# control_board.net
KiCad netlist of a schematic drawn in EAGLE
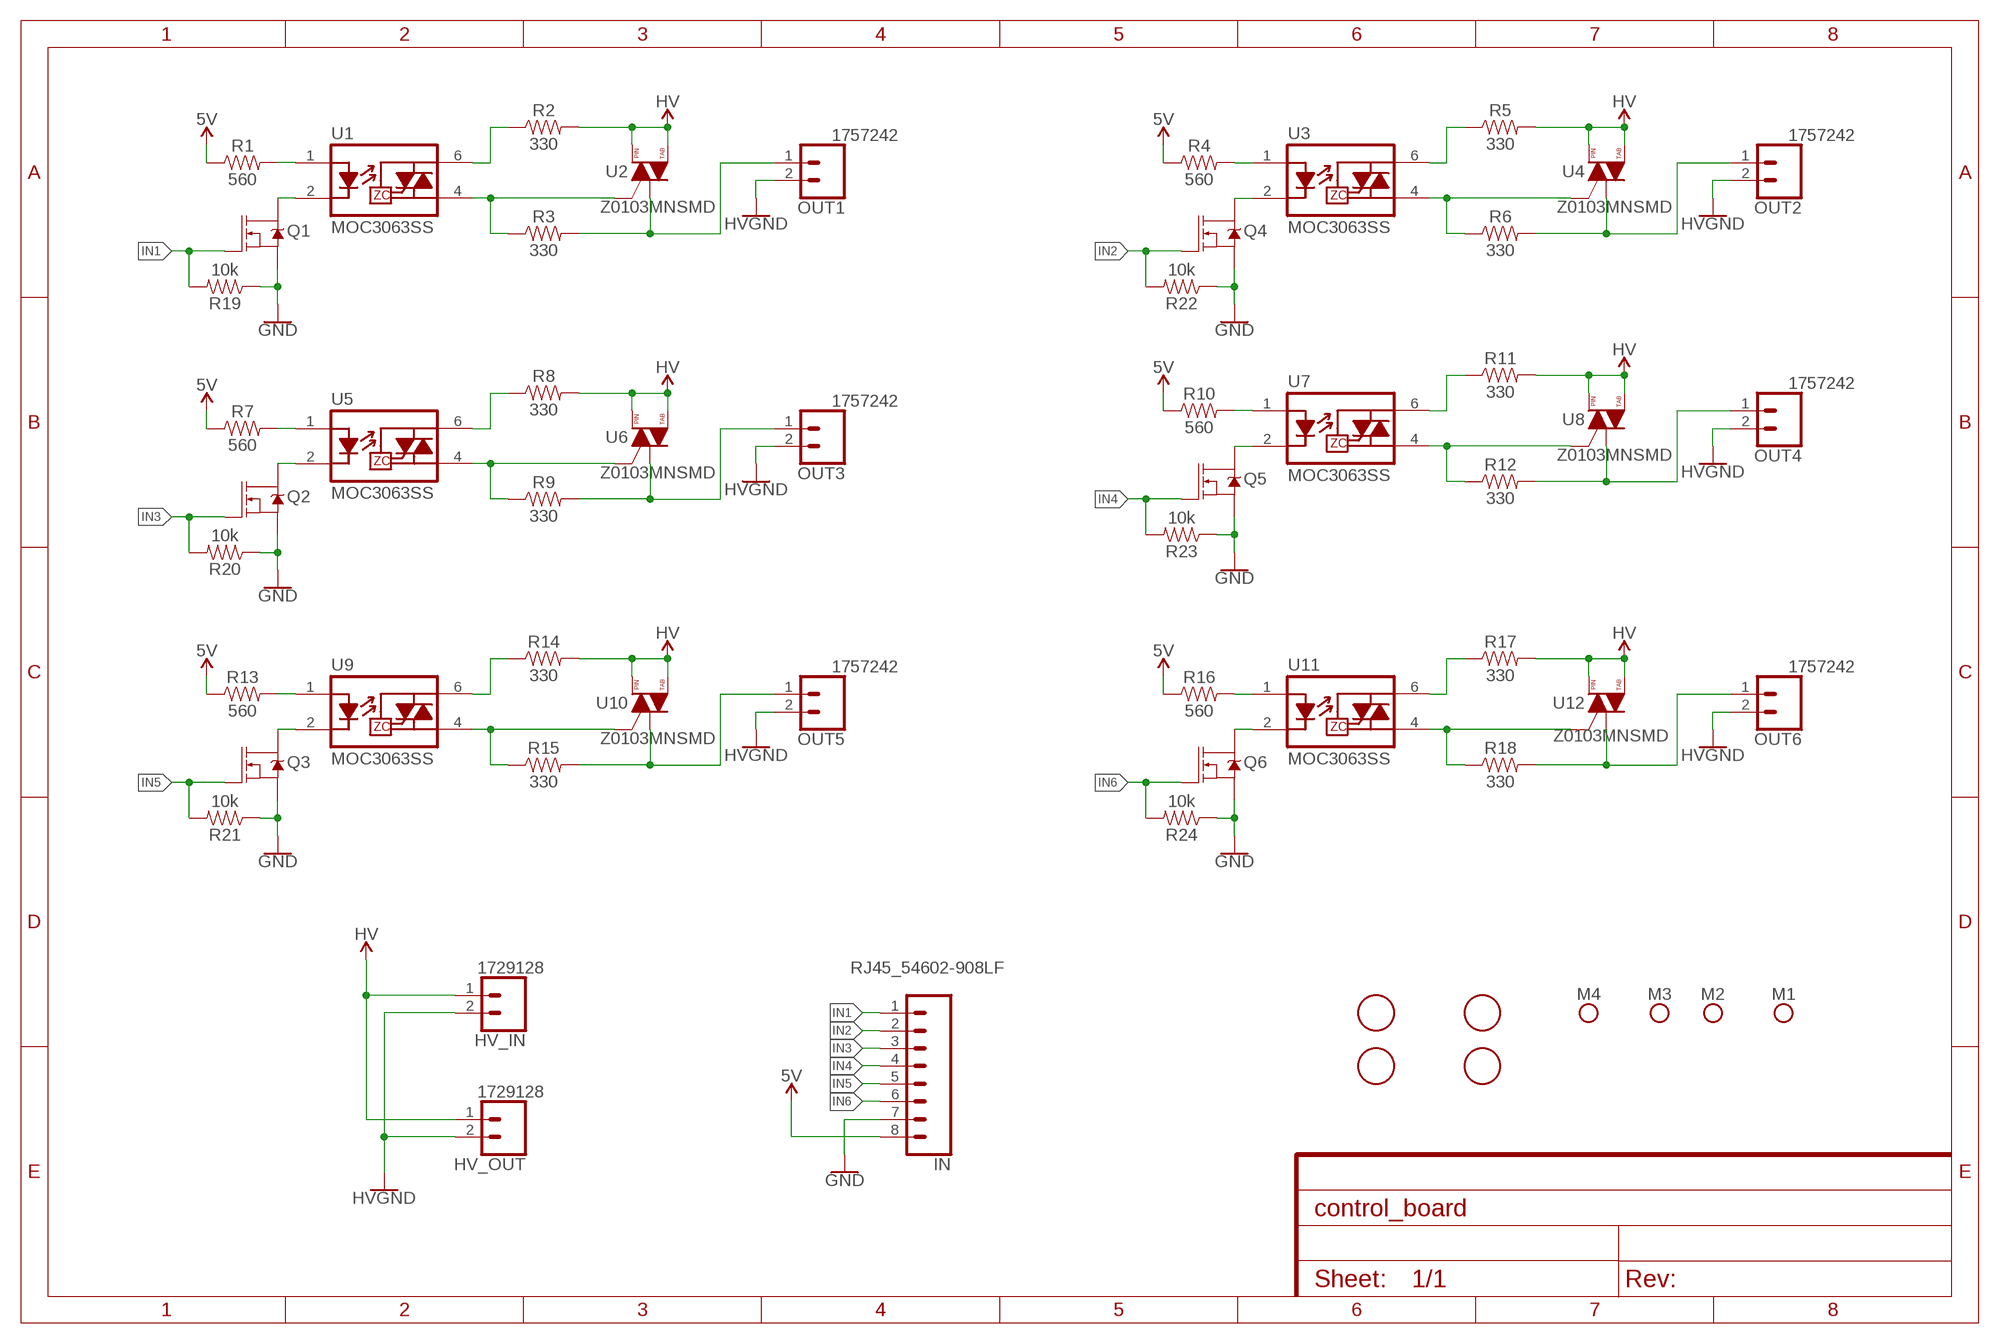
[diagram p0: schematic, sheet 1]

(export (version "E")
  (design (tool "Eeschema 10.0.6"))
  (components
    (comp (ref "HV_IN")
      (value "1729128")
      (footprint "eagle-import:1729128")
      (fields (field (name "MOUSER_PART_NUMBER") "651-1729128"))
      (libsource (lib "eagle-import") (part "1729128"))
    )
    (comp (ref "HV_OUT")
      (value "1729128")
      (footprint "eagle-import:1729128")
      (fields (field (name "MOUSER_PART_NUMBER") "651-1729128"))
      (libsource (lib "eagle-import") (part "1729128"))
    )
    (comp (ref "IN")
      (value "RJ45_54602-908LF")
      (footprint "eagle-import:54602-908LF")
      (fields
        (field (name "MANUFACTURER_PART_NUMBER") "54602-908LF")
        (field (name "JLC_PART_NUMBER") "C2847314")
      )
      (libsource (lib "eagle-import") (part "RJ45_54602-908LF"))
    )
    (comp (ref "M1")
      (value "NO_BOM")
      (footprint "eagle-import:HOLE_ISOLATED_M2.5")
      (libsource (lib "eagle-import") (part "HOLE_ISOLATED-M2.5"))
    )
    (comp (ref "M2")
      (value "NO_BOM")
      (footprint "eagle-import:HOLE_ISOLATED_M2.5")
      (libsource (lib "eagle-import") (part "HOLE_ISOLATED-M2.5"))
    )
    (comp (ref "M3")
      (value "NO_BOM")
      (footprint "eagle-import:HOLE_ISOLATED_M2.5")
      (libsource (lib "eagle-import") (part "HOLE_ISOLATED-M2.5"))
    )
    (comp (ref "M4")
      (value "NO_BOM")
      (footprint "eagle-import:HOLE_ISOLATED_M2.5")
      (libsource (lib "eagle-import") (part "HOLE_ISOLATED-M2.5"))
    )
    (comp (ref "OUT1")
      (value "1757242")
      (footprint "eagle-import:PHOENIX_1757242")
      (fields (field (name "DIGI-KEY_PART_NUMBER") "277-1106-ND") (field (name "JLC_PART_NUMBER") "C90074"))
      (libsource (lib "eagle-import") (part "1757242"))
    )
    (comp (ref "OUT2")
      (value "1757242")
      (footprint "eagle-import:PHOENIX_1757242")
      (fields (field (name "DIGI-KEY_PART_NUMBER") "277-1106-ND") (field (name "JLC_PART_NUMBER") "C90074"))
      (libsource (lib "eagle-import") (part "1757242"))
    )
    (comp (ref "OUT3")
      (value "1757242")
      (footprint "eagle-import:PHOENIX_1757242")
      (fields (field (name "DIGI-KEY_PART_NUMBER") "277-1106-ND") (field (name "JLC_PART_NUMBER") "C90074"))
      (libsource (lib "eagle-import") (part "1757242"))
    )
    (comp (ref "OUT4")
      (value "1757242")
      (footprint "eagle-import:PHOENIX_1757242")
      (fields (field (name "DIGI-KEY_PART_NUMBER") "277-1106-ND") (field (name "JLC_PART_NUMBER") "C90074"))
      (libsource (lib "eagle-import") (part "1757242"))
    )
    (comp (ref "OUT5")
      (value "1757242")
      (footprint "eagle-import:PHOENIX_1757242")
      (fields (field (name "DIGI-KEY_PART_NUMBER") "277-1106-ND") (field (name "JLC_PART_NUMBER") "C90074"))
      (libsource (lib "eagle-import") (part "1757242"))
    )
    (comp (ref "OUT6")
      (value "1757242")
      (footprint "eagle-import:PHOENIX_1757242")
      (fields (field (name "DIGI-KEY_PART_NUMBER") "277-1106-ND") (field (name "JLC_PART_NUMBER") "C90074"))
      (libsource (lib "eagle-import") (part "1757242"))
    )
    (comp (ref "Q1")
      (value "AO3400A")
      (footprint "eagle-import:SOT95P280X125-3N")
      (fields (field (name "JLC_PART_NUMBER") "C20917"))
      (libsource (lib "eagle-import") (part "AO3400A"))
    )
    (comp (ref "Q2")
      (value "AO3400A")
      (footprint "eagle-import:SOT95P280X125-3N")
      (fields (field (name "JLC_PART_NUMBER") "C20917"))
      (libsource (lib "eagle-import") (part "AO3400A"))
    )
    (comp (ref "Q3")
      (value "AO3400A")
      (footprint "eagle-import:SOT95P280X125-3N")
      (fields (field (name "JLC_PART_NUMBER") "C20917"))
      (libsource (lib "eagle-import") (part "AO3400A"))
    )
    (comp (ref "Q4")
      (value "AO3400A")
      (footprint "eagle-import:SOT95P280X125-3N")
      (fields (field (name "JLC_PART_NUMBER") "C20917"))
      (libsource (lib "eagle-import") (part "AO3400A"))
    )
    (comp (ref "Q5")
      (value "AO3400A")
      (footprint "eagle-import:SOT95P280X125-3N")
      (fields (field (name "JLC_PART_NUMBER") "C20917"))
      (libsource (lib "eagle-import") (part "AO3400A"))
    )
    (comp (ref "Q6")
      (value "AO3400A")
      (footprint "eagle-import:SOT95P280X125-3N")
      (fields (field (name "JLC_PART_NUMBER") "C20917"))
      (libsource (lib "eagle-import") (part "AO3400A"))
    )
    (comp (ref "R1")
      (value "560")
      (footprint "eagle-import:R0603")
      (fields (field (name "JLC_PART_NUMBER") "C23204"))
      (libsource (lib "eagle-import") (part "RES-1/10W-5%-0603"))
    )
    (comp (ref "R2")
      (value "330")
      (footprint "eagle-import:R0603")
      (fields (field (name "JLC_PART_NUMBER") "C23138"))
      (libsource (lib "eagle-import") (part "RES-1/10W-5%-0603"))
    )
    (comp (ref "R3")
      (value "330")
      (footprint "eagle-import:R0603")
      (fields (field (name "JLC_PART_NUMBER") "C23138"))
      (libsource (lib "eagle-import") (part "RES-1/10W-5%-0603"))
    )
    (comp (ref "R4")
      (value "560")
      (footprint "eagle-import:R0603")
      (fields (field (name "JLC_PART_NUMBER") "C23204"))
      (libsource (lib "eagle-import") (part "RES-1/10W-5%-0603"))
    )
    (comp (ref "R5")
      (value "330")
      (footprint "eagle-import:R0603")
      (fields (field (name "JLC_PART_NUMBER") "C23138"))
      (libsource (lib "eagle-import") (part "RES-1/10W-5%-0603"))
    )
    (comp (ref "R6")
      (value "330")
      (footprint "eagle-import:R0603")
      (fields (field (name "JLC_PART_NUMBER") "C23138"))
      (libsource (lib "eagle-import") (part "RES-1/10W-5%-0603"))
    )
    (comp (ref "R7")
      (value "560")
      (footprint "eagle-import:R0603")
      (fields (field (name "JLC_PART_NUMBER") "C23204"))
      (libsource (lib "eagle-import") (part "RES-1/10W-5%-0603"))
    )
    (comp (ref "R8")
      (value "330")
      (footprint "eagle-import:R0603")
      (fields (field (name "JLC_PART_NUMBER") "C23138"))
      (libsource (lib "eagle-import") (part "RES-1/10W-5%-0603"))
    )
    (comp (ref "R9")
      (value "330")
      (footprint "eagle-import:R0603")
      (fields (field (name "JLC_PART_NUMBER") "C23138"))
      (libsource (lib "eagle-import") (part "RES-1/10W-5%-0603"))
    )
    (comp (ref "R10")
      (value "560")
      (footprint "eagle-import:R0603")
      (fields (field (name "JLC_PART_NUMBER") "C23204"))
      (libsource (lib "eagle-import") (part "RES-1/10W-5%-0603"))
    )
    (comp (ref "R11")
      (value "330")
      (footprint "eagle-import:R0603")
      (fields (field (name "JLC_PART_NUMBER") "C23138"))
      (libsource (lib "eagle-import") (part "RES-1/10W-5%-0603"))
    )
    (comp (ref "R12")
      (value "330")
      (footprint "eagle-import:R0603")
      (fields (field (name "JLC_PART_NUMBER") "C23138"))
      (libsource (lib "eagle-import") (part "RES-1/10W-5%-0603"))
    )
    (comp (ref "R13")
      (value "560")
      (footprint "eagle-import:R0603")
      (fields (field (name "JLC_PART_NUMBER") "C23204"))
      (libsource (lib "eagle-import") (part "RES-1/10W-5%-0603"))
    )
    (comp (ref "R14")
      (value "330")
      (footprint "eagle-import:R0603")
      (fields (field (name "JLC_PART_NUMBER") "C23138"))
      (libsource (lib "eagle-import") (part "RES-1/10W-5%-0603"))
    )
    (comp (ref "R15")
      (value "330")
      (footprint "eagle-import:R0603")
      (fields (field (name "JLC_PART_NUMBER") "C23138"))
      (libsource (lib "eagle-import") (part "RES-1/10W-5%-0603"))
    )
    (comp (ref "R16")
      (value "560")
      (footprint "eagle-import:R0603")
      (fields (field (name "JLC_PART_NUMBER") "C23204"))
      (libsource (lib "eagle-import") (part "RES-1/10W-5%-0603"))
    )
    (comp (ref "R17")
      (value "330")
      (footprint "eagle-import:R0603")
      (fields (field (name "JLC_PART_NUMBER") "C23138"))
      (libsource (lib "eagle-import") (part "RES-1/10W-5%-0603"))
    )
    (comp (ref "R18")
      (value "330")
      (footprint "eagle-import:R0603")
      (fields (field (name "JLC_PART_NUMBER") "C23138"))
      (libsource (lib "eagle-import") (part "RES-1/10W-5%-0603"))
    )
    (comp (ref "R19")
      (value "10k")
      (footprint "eagle-import:R0603")
      (fields (field (name "JLC_PART_NUMBER") "C25804"))
      (libsource (lib "eagle-import") (part "RES-1/10W-5%-0603"))
    )
    (comp (ref "R20")
      (value "10k")
      (footprint "eagle-import:R0603")
      (fields (field (name "JLC_PART_NUMBER") "C25804"))
      (libsource (lib "eagle-import") (part "RES-1/10W-5%-0603"))
    )
    (comp (ref "R21")
      (value "10k")
      (footprint "eagle-import:R0603")
      (fields (field (name "JLC_PART_NUMBER") "C25804"))
      (libsource (lib "eagle-import") (part "RES-1/10W-5%-0603"))
    )
    (comp (ref "R22")
      (value "10k")
      (footprint "eagle-import:R0603")
      (fields (field (name "JLC_PART_NUMBER") "C25804"))
      (libsource (lib "eagle-import") (part "RES-1/10W-5%-0603"))
    )
    (comp (ref "R23")
      (value "10k")
      (footprint "eagle-import:R0603")
      (fields (field (name "JLC_PART_NUMBER") "C25804"))
      (libsource (lib "eagle-import") (part "RES-1/10W-5%-0603"))
    )
    (comp (ref "R24")
      (value "10k")
      (footprint "eagle-import:R0603")
      (fields (field (name "JLC_PART_NUMBER") "C25804"))
      (libsource (lib "eagle-import") (part "RES-1/10W-5%-0603"))
    )
    (comp (ref "T1")
      (value "NO_BOM")
      (footprint "eagle-import:JLC_TOOLING_HOLE")
      (libsource (lib "eagle-import") (part "JLC_TOOLING_HOLE"))
    )
    (comp (ref "T2")
      (value "NO_BOM")
      (footprint "eagle-import:JLC_TOOLING_HOLE")
      (libsource (lib "eagle-import") (part "JLC_TOOLING_HOLE"))
    )
    (comp (ref "T3")
      (value "NO_BOM")
      (footprint "eagle-import:JLC_TOOLING_HOLE")
      (libsource (lib "eagle-import") (part "JLC_TOOLING_HOLE"))
    )
    (comp (ref "T4")
      (value "NO_BOM")
      (footprint "eagle-import:JLC_TOOLING_HOLE")
      (libsource (lib "eagle-import") (part "JLC_TOOLING_HOLE"))
    )
    (comp (ref "U1")
      (value "MOC3063SS")
      (footprint "eagle-import:DIP8SMD")
      (fields (field (name "MANUFACTURER_PART_NUMBER") "MOC3063S") (field (name "JLC_PART_NUMBER") "C77950"))
      (libsource (lib "eagle-import") (part "MOC3063SS"))
    )
    (comp (ref "U2")
      (value "Z0103MNSMD")
      (footprint "eagle-import:SOT223")
      (fields
        (field (name "MANUFACTURER_PART_NUMBER") "Z0103MN 5AA4")
        (field (name "JLC_PART_NUMBER") "C163595")
      )
      (libsource (lib "eagle-import") (part "Z0103MNSMD"))
    )
    (comp (ref "U3")
      (value "MOC3063SS")
      (footprint "eagle-import:DIP8SMD")
      (fields (field (name "MANUFACTURER_PART_NUMBER") "MOC3063S") (field (name "JLC_PART_NUMBER") "C77950"))
      (libsource (lib "eagle-import") (part "MOC3063SS"))
    )
    (comp (ref "U4")
      (value "Z0103MNSMD")
      (footprint "eagle-import:SOT223")
      (fields
        (field (name "MANUFACTURER_PART_NUMBER") "Z0103MN 5AA4")
        (field (name "JLC_PART_NUMBER") "C163595")
      )
      (libsource (lib "eagle-import") (part "Z0103MNSMD"))
    )
    (comp (ref "U5")
      (value "MOC3063SS")
      (footprint "eagle-import:DIP8SMD")
      (fields (field (name "MANUFACTURER_PART_NUMBER") "MOC3063S") (field (name "JLC_PART_NUMBER") "C77950"))
      (libsource (lib "eagle-import") (part "MOC3063SS"))
    )
    (comp (ref "U6")
      (value "Z0103MNSMD")
      (footprint "eagle-import:SOT223")
      (fields
        (field (name "MANUFACTURER_PART_NUMBER") "Z0103MN 5AA4")
        (field (name "JLC_PART_NUMBER") "C163595")
      )
      (libsource (lib "eagle-import") (part "Z0103MNSMD"))
    )
    (comp (ref "U7")
      (value "MOC3063SS")
      (footprint "eagle-import:DIP8SMD")
      (fields (field (name "MANUFACTURER_PART_NUMBER") "MOC3063S") (field (name "JLC_PART_NUMBER") "C77950"))
      (libsource (lib "eagle-import") (part "MOC3063SS"))
    )
    (comp (ref "U8")
      (value "Z0103MNSMD")
      (footprint "eagle-import:SOT223")
      (fields
        (field (name "MANUFACTURER_PART_NUMBER") "Z0103MN 5AA4")
        (field (name "JLC_PART_NUMBER") "C163595")
      )
      (libsource (lib "eagle-import") (part "Z0103MNSMD"))
    )
    (comp (ref "U9")
      (value "MOC3063SS")
      (footprint "eagle-import:DIP8SMD")
      (fields (field (name "MANUFACTURER_PART_NUMBER") "MOC3063S") (field (name "JLC_PART_NUMBER") "C77950"))
      (libsource (lib "eagle-import") (part "MOC3063SS"))
    )
    (comp (ref "U10")
      (value "Z0103MNSMD")
      (footprint "eagle-import:SOT223")
      (fields
        (field (name "MANUFACTURER_PART_NUMBER") "Z0103MN 5AA4")
        (field (name "JLC_PART_NUMBER") "C163595")
      )
      (libsource (lib "eagle-import") (part "Z0103MNSMD"))
    )
    (comp (ref "U11")
      (value "MOC3063SS")
      (footprint "eagle-import:DIP8SMD")
      (fields (field (name "MANUFACTURER_PART_NUMBER") "MOC3063S") (field (name "JLC_PART_NUMBER") "C77950"))
      (libsource (lib "eagle-import") (part "MOC3063SS"))
    )
    (comp (ref "U12")
      (value "Z0103MNSMD")
      (footprint "eagle-import:SOT223")
      (fields
        (field (name "MANUFACTURER_PART_NUMBER") "Z0103MN 5AA4")
        (field (name "JLC_PART_NUMBER") "C163595")
      )
      (libsource (lib "eagle-import") (part "Z0103MNSMD"))
    )
  )
  (nets
    (net (code "1") (name "5V") (class "Default")
      (node (ref "IN") (pin "8") (pinfunction "8_8") (pintype "passive"))
      (node (ref "R1") (pin "1") (pinfunction "1_1") (pintype "passive"))
      (node (ref "R10") (pin "1") (pinfunction "1_1") (pintype "passive"))
      (node (ref "R13") (pin "1") (pinfunction "1_1") (pintype "passive"))
      (node (ref "R16") (pin "1") (pinfunction "1_1") (pintype "passive"))
      (node (ref "R4") (pin "1") (pinfunction "1_1") (pintype "passive"))
      (node (ref "R7") (pin "1") (pinfunction "1_1") (pintype "passive"))
    )
    (net (code "2") (name "GND") (class "Default")
      (node (ref "IN") (pin "7") (pinfunction "7_7") (pintype "passive"))
      (node (ref "Q1") (pin "2") (pinfunction "S_2") (pintype "passive"))
      (node (ref "Q2") (pin "2") (pinfunction "S_2") (pintype "passive"))
      (node (ref "Q3") (pin "2") (pinfunction "S_2") (pintype "passive"))
      (node (ref "Q4") (pin "2") (pinfunction "S_2") (pintype "passive"))
      (node (ref "Q5") (pin "2") (pinfunction "S_2") (pintype "passive"))
      (node (ref "Q6") (pin "2") (pinfunction "S_2") (pintype "passive"))
      (node (ref "R19") (pin "1") (pinfunction "1_1") (pintype "passive"))
      (node (ref "R20") (pin "1") (pinfunction "1_1") (pintype "passive"))
      (node (ref "R21") (pin "1") (pinfunction "1_1") (pintype "passive"))
      (node (ref "R22") (pin "1") (pinfunction "1_1") (pintype "passive"))
      (node (ref "R23") (pin "1") (pinfunction "1_1") (pintype "passive"))
      (node (ref "R24") (pin "1") (pinfunction "1_1") (pintype "passive"))
    )
    (net (code "3") (name "HV") (class "Default")
      (node (ref "HV_IN") (pin "1") (pinfunction "1_1") (pintype "passive"))
      (node (ref "HV_OUT") (pin "1") (pinfunction "1_1") (pintype "passive"))
      (node (ref "R11") (pin "2") (pinfunction "2_2") (pintype "passive"))
      (node (ref "R14") (pin "2") (pinfunction "2_2") (pintype "passive"))
      (node (ref "R17") (pin "2") (pinfunction "2_2") (pintype "passive"))
      (node (ref "R2") (pin "2") (pinfunction "2_2") (pintype "passive"))
      (node (ref "R5") (pin "2") (pinfunction "2_2") (pintype "passive"))
      (node (ref "R8") (pin "2") (pinfunction "2_2") (pintype "passive"))
      (node (ref "U10") (pin "2") (pinfunction "T2_2") (pintype "passive"))
      (node (ref "U10") (pin "4") (pinfunction "T2_4") (pintype "passive"))
      (node (ref "U12") (pin "2") (pinfunction "T2_2") (pintype "passive"))
      (node (ref "U12") (pin "4") (pinfunction "T2_4") (pintype "passive"))
      (node (ref "U2") (pin "2") (pinfunction "T2_2") (pintype "passive"))
      (node (ref "U2") (pin "4") (pinfunction "T2_4") (pintype "passive"))
      (node (ref "U4") (pin "2") (pinfunction "T2_2") (pintype "passive"))
      (node (ref "U4") (pin "4") (pinfunction "T2_4") (pintype "passive"))
      (node (ref "U6") (pin "2") (pinfunction "T2_2") (pintype "passive"))
      (node (ref "U6") (pin "4") (pinfunction "T2_4") (pintype "passive"))
      (node (ref "U8") (pin "2") (pinfunction "T2_2") (pintype "passive"))
      (node (ref "U8") (pin "4") (pinfunction "T2_4") (pintype "passive"))
    )
    (net (code "4") (name "HVGND") (class "Default")
      (node (ref "HV_IN") (pin "2") (pinfunction "2_2") (pintype "passive"))
      (node (ref "HV_OUT") (pin "2") (pinfunction "2_2") (pintype "passive"))
      (node (ref "OUT1") (pin "2") (pinfunction "2_2") (pintype "passive"))
      (node (ref "OUT2") (pin "2") (pinfunction "2_2") (pintype "passive"))
      (node (ref "OUT3") (pin "2") (pinfunction "2_2") (pintype "passive"))
      (node (ref "OUT4") (pin "2") (pinfunction "2_2") (pintype "passive"))
      (node (ref "OUT5") (pin "2") (pinfunction "2_2") (pintype "passive"))
      (node (ref "OUT6") (pin "2") (pinfunction "2_2") (pintype "passive"))
    )
    (net (code "5") (name "IN1") (class "Default")
      (node (ref "IN") (pin "1") (pinfunction "1_1") (pintype "passive"))
      (node (ref "Q1") (pin "1") (pinfunction "G_1") (pintype "passive"))
      (node (ref "R19") (pin "2") (pinfunction "2_2") (pintype "passive"))
    )
    (net (code "6") (name "IN2") (class "Default")
      (node (ref "IN") (pin "2") (pinfunction "2_2") (pintype "passive"))
      (node (ref "Q4") (pin "1") (pinfunction "G_1") (pintype "passive"))
      (node (ref "R22") (pin "2") (pinfunction "2_2") (pintype "passive"))
    )
    (net (code "7") (name "IN3") (class "Default")
      (node (ref "IN") (pin "3") (pinfunction "3_3") (pintype "passive"))
      (node (ref "Q2") (pin "1") (pinfunction "G_1") (pintype "passive"))
      (node (ref "R20") (pin "2") (pinfunction "2_2") (pintype "passive"))
    )
    (net (code "8") (name "IN4") (class "Default")
      (node (ref "IN") (pin "4") (pinfunction "4_4") (pintype "passive"))
      (node (ref "Q5") (pin "1") (pinfunction "G_1") (pintype "passive"))
      (node (ref "R23") (pin "2") (pinfunction "2_2") (pintype "passive"))
    )
    (net (code "9") (name "IN5") (class "Default")
      (node (ref "IN") (pin "5") (pinfunction "5_5") (pintype "passive"))
      (node (ref "Q3") (pin "1") (pinfunction "G_1") (pintype "passive"))
      (node (ref "R21") (pin "2") (pinfunction "2_2") (pintype "passive"))
    )
    (net (code "10") (name "IN6") (class "Default")
      (node (ref "IN") (pin "6") (pinfunction "6_6") (pintype "passive"))
      (node (ref "Q6") (pin "1") (pinfunction "G_1") (pintype "passive"))
      (node (ref "R24") (pin "2") (pinfunction "2_2") (pintype "passive"))
    )
    (net (code "11") (name "Net-(Q1-D)") (class "Default")
      (node (ref "Q1") (pin "3") (pinfunction "D_3") (pintype "passive"))
      (node (ref "U1") (pin "2") (pinfunction "K_2") (pintype "bidirectional"))
    )
    (net (code "12") (name "Net-(Q2-D)") (class "Default")
      (node (ref "Q2") (pin "3") (pinfunction "D_3") (pintype "passive"))
      (node (ref "U5") (pin "2") (pinfunction "K_2") (pintype "bidirectional"))
    )
    (net (code "13") (name "Net-(Q3-D)") (class "Default")
      (node (ref "Q3") (pin "3") (pinfunction "D_3") (pintype "passive"))
      (node (ref "U9") (pin "2") (pinfunction "K_2") (pintype "bidirectional"))
    )
    (net (code "14") (name "Net-(Q4-D)") (class "Default")
      (node (ref "Q4") (pin "3") (pinfunction "D_3") (pintype "passive"))
      (node (ref "U3") (pin "2") (pinfunction "K_2") (pintype "bidirectional"))
    )
    (net (code "15") (name "Net-(Q5-D)") (class "Default")
      (node (ref "Q5") (pin "3") (pinfunction "D_3") (pintype "passive"))
      (node (ref "U7") (pin "2") (pinfunction "K_2") (pintype "bidirectional"))
    )
    (net (code "16") (name "Net-(Q6-D)") (class "Default")
      (node (ref "Q6") (pin "3") (pinfunction "D_3") (pintype "passive"))
      (node (ref "U11") (pin "2") (pinfunction "K_2") (pintype "bidirectional"))
    )
    (net (code "17") (name "Net-(U1-A)") (class "Default")
      (node (ref "R1") (pin "2") (pinfunction "2_2") (pintype "passive"))
      (node (ref "U1") (pin "1") (pinfunction "A_1") (pintype "bidirectional"))
    )
    (net (code "18") (name "Net-(U1-T1)") (class "Default")
      (node (ref "R2") (pin "1") (pinfunction "1_1") (pintype "passive"))
      (node (ref "U1") (pin "6") (pinfunction "T1_6") (pintype "bidirectional"))
    )
    (net (code "19") (name "Net-(U1-T2)") (class "Default")
      (node (ref "R3") (pin "1") (pinfunction "1_1") (pintype "passive"))
      (node (ref "U1") (pin "4") (pinfunction "T2_4") (pintype "bidirectional"))
      (node (ref "U2") (pin "3") (pinfunction "G_3") (pintype "bidirectional"))
    )
    (net (code "20") (name "Net-(U2-T1)") (class "Default")
      (node (ref "OUT1") (pin "1") (pinfunction "1_1") (pintype "passive"))
      (node (ref "R3") (pin "2") (pinfunction "2_2") (pintype "passive"))
      (node (ref "U2") (pin "1") (pinfunction "T1_1") (pintype "bidirectional"))
    )
    (net (code "21") (name "Net-(U3-A)") (class "Default")
      (node (ref "R4") (pin "2") (pinfunction "2_2") (pintype "passive"))
      (node (ref "U3") (pin "1") (pinfunction "A_1") (pintype "bidirectional"))
    )
    (net (code "22") (name "Net-(U3-T1)") (class "Default")
      (node (ref "R5") (pin "1") (pinfunction "1_1") (pintype "passive"))
      (node (ref "U3") (pin "6") (pinfunction "T1_6") (pintype "bidirectional"))
    )
    (net (code "23") (name "Net-(U3-T2)") (class "Default")
      (node (ref "R6") (pin "1") (pinfunction "1_1") (pintype "passive"))
      (node (ref "U3") (pin "4") (pinfunction "T2_4") (pintype "bidirectional"))
      (node (ref "U4") (pin "3") (pinfunction "G_3") (pintype "bidirectional"))
    )
    (net (code "24") (name "Net-(U4-T1)") (class "Default")
      (node (ref "OUT2") (pin "1") (pinfunction "1_1") (pintype "passive"))
      (node (ref "R6") (pin "2") (pinfunction "2_2") (pintype "passive"))
      (node (ref "U4") (pin "1") (pinfunction "T1_1") (pintype "bidirectional"))
    )
    (net (code "25") (name "Net-(U5-A)") (class "Default")
      (node (ref "R7") (pin "2") (pinfunction "2_2") (pintype "passive"))
      (node (ref "U5") (pin "1") (pinfunction "A_1") (pintype "bidirectional"))
    )
    (net (code "26") (name "Net-(U5-T1)") (class "Default")
      (node (ref "R8") (pin "1") (pinfunction "1_1") (pintype "passive"))
      (node (ref "U5") (pin "6") (pinfunction "T1_6") (pintype "bidirectional"))
    )
    (net (code "27") (name "Net-(U5-T2)") (class "Default")
      (node (ref "R9") (pin "1") (pinfunction "1_1") (pintype "passive"))
      (node (ref "U5") (pin "4") (pinfunction "T2_4") (pintype "bidirectional"))
      (node (ref "U6") (pin "3") (pinfunction "G_3") (pintype "bidirectional"))
    )
    (net (code "28") (name "Net-(U6-T1)") (class "Default")
      (node (ref "OUT3") (pin "1") (pinfunction "1_1") (pintype "passive"))
      (node (ref "R9") (pin "2") (pinfunction "2_2") (pintype "passive"))
      (node (ref "U6") (pin "1") (pinfunction "T1_1") (pintype "bidirectional"))
    )
    (net (code "29") (name "Net-(U7-A)") (class "Default")
      (node (ref "R10") (pin "2") (pinfunction "2_2") (pintype "passive"))
      (node (ref "U7") (pin "1") (pinfunction "A_1") (pintype "bidirectional"))
    )
    (net (code "30") (name "Net-(U7-T1)") (class "Default")
      (node (ref "R11") (pin "1") (pinfunction "1_1") (pintype "passive"))
      (node (ref "U7") (pin "6") (pinfunction "T1_6") (pintype "bidirectional"))
    )
    (net (code "31") (name "Net-(U7-T2)") (class "Default")
      (node (ref "R12") (pin "1") (pinfunction "1_1") (pintype "passive"))
      (node (ref "U7") (pin "4") (pinfunction "T2_4") (pintype "bidirectional"))
      (node (ref "U8") (pin "3") (pinfunction "G_3") (pintype "bidirectional"))
    )
    (net (code "32") (name "Net-(U8-T1)") (class "Default")
      (node (ref "OUT4") (pin "1") (pinfunction "1_1") (pintype "passive"))
      (node (ref "R12") (pin "2") (pinfunction "2_2") (pintype "passive"))
      (node (ref "U8") (pin "1") (pinfunction "T1_1") (pintype "bidirectional"))
    )
    (net (code "33") (name "Net-(U9-A)") (class "Default")
      (node (ref "R13") (pin "2") (pinfunction "2_2") (pintype "passive"))
      (node (ref "U9") (pin "1") (pinfunction "A_1") (pintype "bidirectional"))
    )
    (net (code "34") (name "Net-(U9-T1)") (class "Default")
      (node (ref "R14") (pin "1") (pinfunction "1_1") (pintype "passive"))
      (node (ref "U9") (pin "6") (pinfunction "T1_6") (pintype "bidirectional"))
    )
    (net (code "35") (name "Net-(U10-G)") (class "Default")
      (node (ref "R15") (pin "1") (pinfunction "1_1") (pintype "passive"))
      (node (ref "U10") (pin "3") (pinfunction "G_3") (pintype "bidirectional"))
      (node (ref "U9") (pin "4") (pinfunction "T2_4") (pintype "bidirectional"))
    )
    (net (code "36") (name "Net-(U10-T1)") (class "Default")
      (node (ref "OUT5") (pin "1") (pinfunction "1_1") (pintype "passive"))
      (node (ref "R15") (pin "2") (pinfunction "2_2") (pintype "passive"))
      (node (ref "U10") (pin "1") (pinfunction "T1_1") (pintype "bidirectional"))
    )
    (net (code "37") (name "Net-(U11-A)") (class "Default")
      (node (ref "R16") (pin "2") (pinfunction "2_2") (pintype "passive"))
      (node (ref "U11") (pin "1") (pinfunction "A_1") (pintype "bidirectional"))
    )
    (net (code "38") (name "Net-(U11-T1)") (class "Default")
      (node (ref "R17") (pin "1") (pinfunction "1_1") (pintype "passive"))
      (node (ref "U11") (pin "6") (pinfunction "T1_6") (pintype "bidirectional"))
    )
    (net (code "39") (name "Net-(U11-T2)") (class "Default")
      (node (ref "R18") (pin "1") (pinfunction "1_1") (pintype "passive"))
      (node (ref "U11") (pin "4") (pinfunction "T2_4") (pintype "bidirectional"))
      (node (ref "U12") (pin "3") (pinfunction "G_3") (pintype "bidirectional"))
    )
    (net (code "40") (name "Net-(U12-T1)") (class "Default")
      (node (ref "OUT6") (pin "1") (pinfunction "1_1") (pintype "passive"))
      (node (ref "R18") (pin "2") (pinfunction "2_2") (pintype "passive"))
      (node (ref "U12") (pin "1") (pinfunction "T1_1") (pintype "bidirectional"))
    )
  )
)
